# simple-bug-bc547.net
KiCad netlist of a schematic drawn in EAGLE
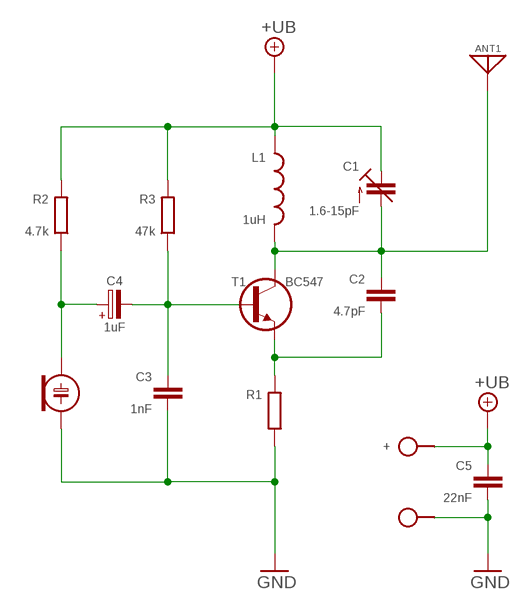
[diagram p0: schematic, sheet 1]

(export (version "E")
  (design (tool "Eeschema 10.0.6"))
  (components
    (comp (ref "+")
      (value "SPAD")
      (footprint "eagle-import:SPAD")
      (libsource (lib "eagle-import") (part "SPAD"))
    )
    (comp (ref "ANT1")
      (value "ANT")
      (footprint "eagle-import:SPAD")
      (libsource (lib "eagle-import") (part "ANT"))
    )
    (comp (ref "C1")
      (value "1.6-15pF")
      (footprint "eagle-import:TRIM-2222-808")
      (libsource (lib "eagle-import") (part "C-TR-PH20127"))
    )
    (comp (ref "C2")
      (value "4.7pF")
      (footprint "eagle-import:C050-020X036")
      (libsource (lib "eagle-import") (part "C050-020X036"))
    )
    (comp (ref "C3")
      (value "1nF")
      (footprint "eagle-import:C050-020X036_V")
      (libsource (lib "eagle-import") (part "C050-020X036/V"))
    )
    (comp (ref "C4")
      (value "1uF")
      (footprint "eagle-import:E2,5-3")
      (libsource (lib "eagle-import") (part "CPOLE2,5-3"))
    )
    (comp (ref "C5")
      (value "22nF")
      (footprint "eagle-import:C050-020X036")
      (libsource (lib "eagle-import") (part "C050-020X036"))
    )
    (comp (ref "ECM")
      (value "ECM-4")
      (footprint "eagle-import:ECM-4")
      (libsource (lib "eagle-import") (part "ECM-4"))
    )
    (comp (ref "L1")
      (value "1uH")
      (footprint "eagle-import:L-04_7V")
      (libsource (lib "eagle-import") (part "L04/7"))
    )
    (comp (ref "R1")
      (value "R0202/5")
      (footprint "eagle-import:0202_5")
      (libsource (lib "eagle-import") (part "R0202/5"))
    )
    (comp (ref "R2")
      (value "4.7k")
      (footprint "eagle-import:0202_5")
      (libsource (lib "eagle-import") (part "R0202/5"))
    )
    (comp (ref "R3")
      (value "47k")
      (footprint "eagle-import:0202_5")
      (libsource (lib "eagle-import") (part "R0202/5"))
    )
    (comp (ref "T1")
      (value "BC547")
      (footprint "eagle-import:TO92-CBE-A")
      (libsource (lib "eagle-import") (part "BC547CBE-A"))
    )
    (comp (ref "̶̶")
      (value "SPAD")
      (footprint "eagle-import:SPAD")
      (libsource (lib "eagle-import") (part "SPAD"))
    )
  )
  (nets
    (net (code "1") (name "+UB") (class "Default")
      (node (ref "+") (pin "1") (pinfunction "P$1_1") (pintype "bidirectional"))
      (node (ref "C1") (pin "1") (pinfunction "E_1") (pintype "passive"))
      (node (ref "C1") (pin "3") (pinfunction "E_3") (pintype "passive"))
      (node (ref "C5") (pin "1") (pinfunction "1_1") (pintype "passive"))
      (node (ref "L1") (pin "1") (pinfunction "1_1") (pintype "passive"))
      (node (ref "R2") (pin "2") (pinfunction "2_2") (pintype "passive"))
      (node (ref "R3") (pin "2") (pinfunction "2_2") (pintype "passive"))
    )
    (net (code "2") (name "GND") (class "Default")
      (node (ref "C3") (pin "2") (pinfunction "2_2") (pintype "passive"))
      (node (ref "C5") (pin "2") (pinfunction "2_2") (pintype "passive"))
      (node (ref "ECM") (pin "2") (pinfunction "-_2") (pintype "passive"))
      (node (ref "R1") (pin "1") (pinfunction "1_1") (pintype "passive"))
      (node (ref "̶̶") (pin "1") (pinfunction "P$1_1") (pintype "bidirectional"))
    )
    (net (code "3") (name "Net-(C1-A)") (class "Default")
      (node (ref "ANT1") (pin "1") (pinfunction "1_1") (pintype "output"))
      (node (ref "C1") (pin "2") (pinfunction "A_2") (pintype "passive"))
      (node (ref "C2") (pin "1") (pinfunction "1_1") (pintype "passive"))
      (node (ref "L1") (pin "2") (pinfunction "2_2") (pintype "passive"))
      (node (ref "T1") (pin "C") (pinfunction "C_C") (pintype "passive"))
    )
    (net (code "4") (name "Net-(C2-Pad2)") (class "Default")
      (node (ref "C2") (pin "2") (pinfunction "2_2") (pintype "passive"))
      (node (ref "R1") (pin "2") (pinfunction "2_2") (pintype "passive"))
      (node (ref "T1") (pin "E") (pinfunction "E_E") (pintype "passive"))
    )
    (net (code "5") (name "Net-(C3-Pad1)") (class "Default")
      (node (ref "C3") (pin "1") (pinfunction "1_1") (pintype "passive"))
      (node (ref "C4") (pin "-") (pinfunction "-_-") (pintype "passive"))
      (node (ref "R3") (pin "1") (pinfunction "1_1") (pintype "passive"))
      (node (ref "T1") (pin "B") (pinfunction "B_B") (pintype "passive"))
    )
    (net (code "6") (name "Net-(ECM-+)") (class "Default")
      (node (ref "C4") (pin "+") (pinfunction "+_+") (pintype "passive"))
      (node (ref "ECM") (pin "1") (pinfunction "+_1") (pintype "passive"))
      (node (ref "R2") (pin "1") (pinfunction "1_1") (pintype "passive"))
    )
  )
)
